# SensorInput.net
KiCad netlist of a schematic drawn in Altium Designer
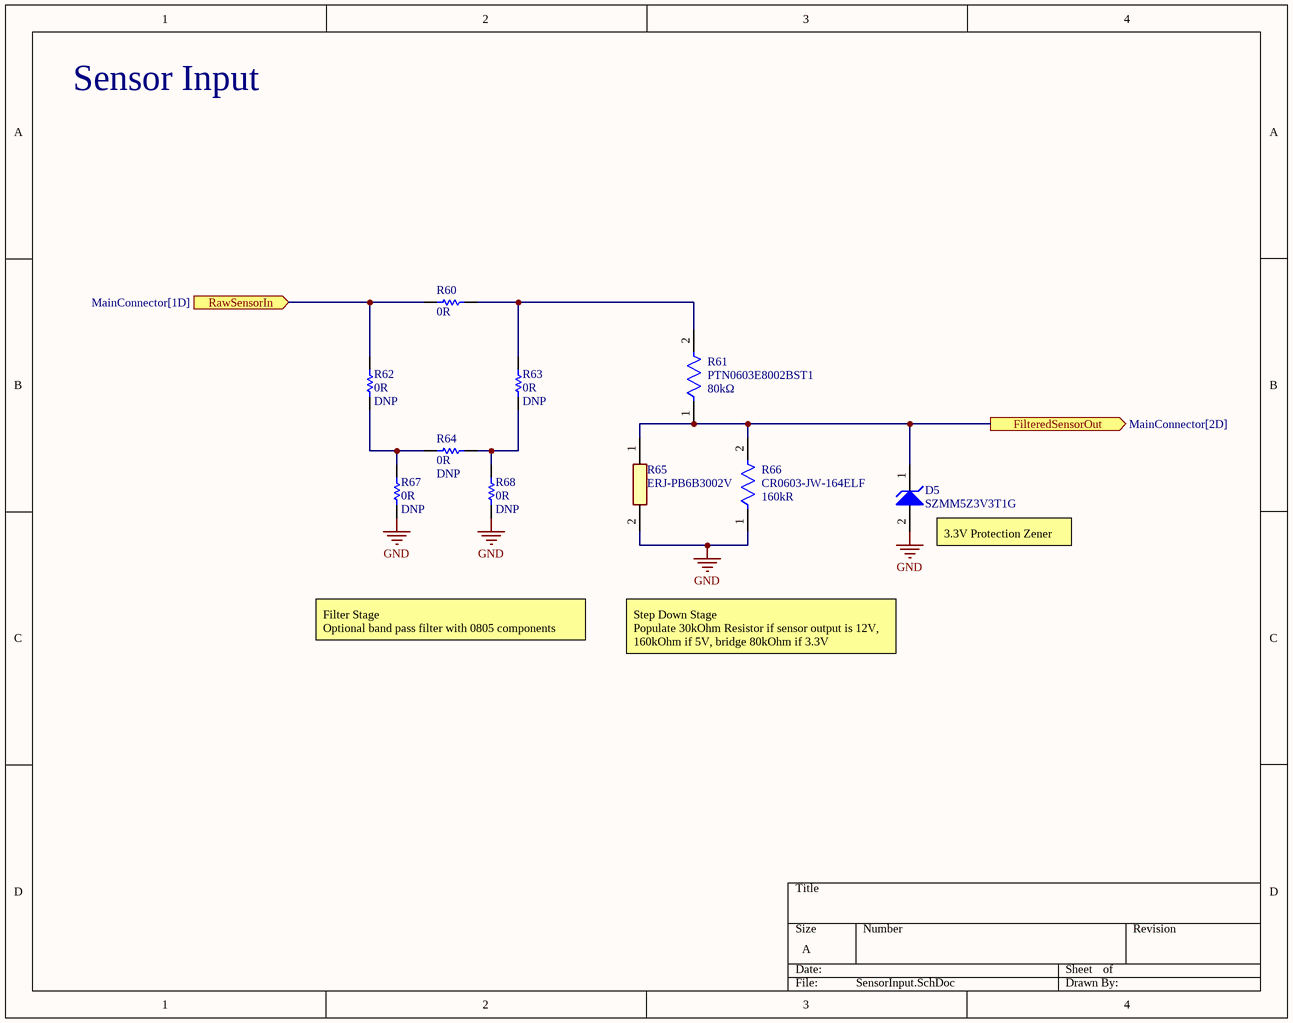
[diagram p0: SensorInput.SchDoc]

(export (version "E")
  (design (tool "Eeschema 10.0.6"))
  (components
    (comp (ref "D5")
      (value "SZMM5Z3V3T1G")
      (footprint "ONSC-SOD-523-2-502-01_V")
      (description "Zener Voltage Regulator, 500 mW, 2-Pin SOD-523, Pb-Free, Tape and Reel")
      (fields (field (name "MANUFACTURER") "On Semiconductor"))
      (libsource (lib "Altium Content Vault") (part "ONSC-K1A2-2"))
    )
    (comp (ref "R60")
      (value "RC0805JR-100RL")
      (footprint "RESC2013X60X35LL10T20")
      (description "Chip Resistor, 0 Ohm, +/- 5%, 125 mW, -55 to 155 degC, 0805 (2012 Metric), RoHS, Tape and Reel")
      (fields (field (name "MANUFACTURER") "Yageo") (field (name "RESISTANCE") "0R"))
      (libsource (lib "Altium Content Vault") (part "RES-2"))
    )
    (comp (ref "R61")
      (value "PTN0603E8002BST1")
      (footprint "FP-PTN0603-MFG")
      (description "RES 80K OHM 0.1% 0.15W 0603")
      (fields
        (field (name "MANUFACTURER") "Vishay")
        (field (name "RESISTANCE") "80kΩ")
        (field (name "TOLERANCE") "0.1%")
      )
      (libsource (lib "Altium Content Vault") (part "1029c3af85768c4190bb7ad29bc67b5"))
    )
    (comp (ref "R62")
      (value "RC0805JR-100RL")
      (footprint "RESC2013X60X35LL10T20")
      (description "Chip Resistor, 0 Ohm, +/- 5%, 125 mW, -55 to 155 degC, 0805 (2012 Metric), RoHS, Tape and Reel")
      (fields
        (field (name "MANUFACTURER") "Yageo")
        (field (name "RESISTANCE") "0R")
        (field (name "DNP") "DNP")
      )
      (libsource (lib "Altium Content Vault") (part "RES-2"))
    )
    (comp (ref "R63")
      (value "RC0805JR-100RL")
      (footprint "RESC2013X60X35LL10T20")
      (description "Chip Resistor, 0 Ohm, +/- 5%, 125 mW, -55 to 155 degC, 0805 (2012 Metric), RoHS, Tape and Reel")
      (fields
        (field (name "MANUFACTURER") "Yageo")
        (field (name "RESISTANCE") "0R")
        (field (name "DNP") "DNP")
      )
      (libsource (lib "Altium Content Vault") (part "RES-2"))
    )
    (comp (ref "R64")
      (value "RC0805JR-100RL")
      (footprint "RESC2013X60X35LL10T20")
      (description "Chip Resistor, 0 Ohm, +/- 5%, 125 mW, -55 to 155 degC, 0805 (2012 Metric), RoHS, Tape and Reel")
      (fields
        (field (name "MANUFACTURER") "Yageo")
        (field (name "RESISTANCE") "0R")
        (field (name "DNP") "DNP")
      )
      (libsource (lib "Altium Content Vault") (part "RES-2"))
    )
    (comp (ref "R65")
      (value "ERJ-PB6B3002V")
      (footprint "SamacSys:RESC2012X70N")
      (description "Resistor")
      (fields (field (name "MOUSER PART NUMBER") "667-ERJ-PB6B3002V"))
      (libsource (lib "*") (part "ERJ-PB6B3002V"))
    )
    (comp (ref "R66")
      (value "CR0603-JW-164ELF")
      (footprint "FP-CR0603-IPC_B")
      (description "Thick Film Chip Resistors 0603 160kΩ 0.1W 5% 200ppm/°C")
      (fields (field (name "TOLERANCE") "5%") (field (name "RESISTANCE") "160kR"))
      (libsource (lib "Altium Content Vault") (part "1029c3af85768c4190bb7ad29bc67b5"))
    )
    (comp (ref "R67")
      (value "RC0805JR-100RL")
      (footprint "RESC2013X60X35LL10T20")
      (description "Chip Resistor, 0 Ohm, +/- 5%, 125 mW, -55 to 155 degC, 0805 (2012 Metric), RoHS, Tape and Reel")
      (fields
        (field (name "MANUFACTURER") "Yageo")
        (field (name "RESISTANCE") "0R")
        (field (name "DNP") "DNP")
      )
      (libsource (lib "Altium Content Vault") (part "RES-2"))
    )
    (comp (ref "R68")
      (value "RC0805JR-100RL")
      (footprint "RESC2013X60X35LL10T20")
      (description "Chip Resistor, 0 Ohm, +/- 5%, 125 mW, -55 to 155 degC, 0805 (2012 Metric), RoHS, Tape and Reel")
      (fields
        (field (name "MANUFACTURER") "Yageo")
        (field (name "RESISTANCE") "0R")
        (field (name "DNP") "DNP")
      )
      (libsource (lib "Altium Content Vault") (part "RES-2"))
    )
  )
  (nets
    (net (code "1") (name "/FilteredSensorOut") (class "Default")
      (node (ref "D5") (pin "1") (pinfunction "K_1") (pintype "passive"))
      (node (ref "R61") (pin "1") (pinfunction "1_1") (pintype "passive"))
      (node (ref "R65") (pin "1") (pinfunction "1_1") (pintype "passive"))
      (node (ref "R66") (pin "2") (pinfunction "2_2") (pintype "passive"))
    )
    (net (code "2") (name "/RawSensorIn") (class "Default")
      (node (ref "R60") (pin "2") (pinfunction "2_2") (pintype "passive"))
      (node (ref "R62") (pin "2") (pinfunction "2_2") (pintype "passive"))
    )
    (net (code "3") (name "GND") (class "Default")
      (node (ref "D5") (pin "2") (pinfunction "A_2") (pintype "passive"))
      (node (ref "R65") (pin "2") (pinfunction "2_2") (pintype "passive"))
      (node (ref "R66") (pin "1") (pinfunction "1_1") (pintype "passive"))
      (node (ref "R67") (pin "2") (pinfunction "2_2") (pintype "passive"))
      (node (ref "R68") (pin "2") (pinfunction "2_2") (pintype "passive"))
    )
    (net (code "4") (name "Net-(R60-Pad1)") (class "Default")
      (node (ref "R60") (pin "1") (pinfunction "1_1") (pintype "passive"))
      (node (ref "R61") (pin "2") (pinfunction "2_2") (pintype "passive"))
      (node (ref "R63") (pin "1") (pinfunction "1_1") (pintype "passive"))
    )
    (net (code "5") (name "Net-(R62-Pad1)") (class "Default")
      (node (ref "R62") (pin "1") (pinfunction "1_1") (pintype "passive"))
      (node (ref "R64") (pin "2") (pinfunction "2_2") (pintype "passive"))
      (node (ref "R67") (pin "1") (pinfunction "1_1") (pintype "passive"))
    )
    (net (code "6") (name "Net-(R63-Pad2)") (class "Default")
      (node (ref "R63") (pin "2") (pinfunction "2_2") (pintype "passive"))
      (node (ref "R64") (pin "1") (pinfunction "1_1") (pintype "passive"))
      (node (ref "R68") (pin "1") (pinfunction "1_1") (pintype "passive"))
    )
  )
)
